# Coin_Cell_Boost.net
KiCad netlist of a schematic drawn in Altium Designer
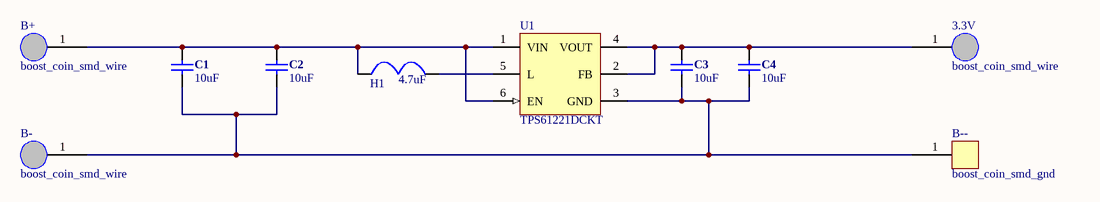
[diagram p0: Coin_Cell_Boost.SchDoc]

(export (version "E")
  (design (tool "Eeschema 10.0.6"))
  (components
    (comp (ref "3.3V")
      (value "boost_coin_smd_wire")
      (footprint "smd_pin")
      (libsource (lib "UVS-Schlib") (part "boost_coin_smd_wire"))
    )
    (comp (ref "B+")
      (value "boost_coin_smd_wire")
      (footprint "smd_pin")
      (libsource (lib "UVS-Schlib") (part "boost_coin_smd_wire"))
    )
    (comp (ref "B-")
      (value "boost_coin_smd_wire")
      (footprint "smd_pin")
      (libsource (lib "UVS-Schlib") (part "boost_coin_smd_wire"))
    )
    (comp (ref "B--")
      (value "boost_coin_smd_gnd")
      (footprint "smd_gnd")
      (libsource (lib "UVS-Schlib") (part "boost_coin_smd_gnd"))
    )
    (comp (ref "C1")
      (value "10uF")
      (footprint "CAP-0805(2012)-R")
      (description "___ OHM ___ mW 0805(2012) SMD")
      (fields
        (field (name "MANUFACTURER") "Murata Electronics North America")
        (field (name "MANUFACTURER PART NUMBER") "GRM21BR60J106ME19L")
      )
      (libsource (lib "Glove") (part "C-0805(2012)"))
    )
    (comp (ref "C2")
      (value "10uF")
      (footprint "CAP-0805(2012)-R")
      (description "___ OHM ___ mW 0805(2012) SMD")
      (fields
        (field (name "MANUFACTURER") "Murata Electronics North America")
        (field (name "MANUFACTURER PART NUMBER") "GRM21BR60J106ME19L")
      )
      (libsource (lib "Glove") (part "C-0805(2012)"))
    )
    (comp (ref "C3")
      (value "10uF")
      (footprint "CAP-0805(2012)-R")
      (description "___ OHM ___ mW 0805(2012) SMD")
      (fields
        (field (name "MANUFACTURER") "Murata Electronics North America")
        (field (name "MANUFACTURER PART NUMBER") "GRM21BR60J106ME19L")
      )
      (libsource (lib "Glove") (part "C-0805(2012)"))
    )
    (comp (ref "C4")
      (value "10uF")
      (footprint "CAP-0805(2012)-R")
      (description "___ OHM ___ mW 0805(2012) SMD")
      (fields
        (field (name "MANUFACTURER") "Murata Electronics North America")
        (field (name "MANUFACTURER PART NUMBER") "GRM21BR60J106ME19L")
      )
      (libsource (lib "Glove") (part "C-0805(2012)"))
    )
    (comp (ref "H1")
      (value "4.7uF")
      (footprint "H-0805(2012)-H")
      (fields
        (field (name "MANUFACTURER") "Murata Electronics North America")
        (field (name "MANUFACTURER PART NUMBER") "LQM21PN4R7NGRD")
        (field (name "TOLERANCE") "±30%")
      )
      (libsource (lib "Glove") (part "H-0805(2012)"))
    )
    (comp (ref "U1")
      (value "TPS61221DCKT")
      (footprint "DCK0006A_L")
      (fields (field (name "MANUFACTURER") "Texas Instruments"))
      (libsource (lib "Altium Content Vault") (part "TI-TPS61221DCK6"))
    )
  )
  (nets
    (net (code "1") (name "Net-(U1-EN)") (class "Default")
      (node (ref "B+") (pin "1") (pinfunction "1_1") (pintype "passive"))
      (node (ref "C1") (pin "1") (pinfunction "1_1") (pintype "passive"))
      (node (ref "C2") (pin "1") (pinfunction "1_1") (pintype "passive"))
      (node (ref "H1") (pin "1") (pinfunction "1_1") (pintype "passive"))
      (node (ref "U1") (pin "1") (pinfunction "VIN_1") (pintype "power_in"))
      (node (ref "U1") (pin "6") (pinfunction "EN_6") (pintype "input"))
    )
    (net (code "2") (name "Net-(U1-FB)") (class "Default")
      (node (ref "3.3V") (pin "1") (pinfunction "1_1") (pintype "passive"))
      (node (ref "C3") (pin "1") (pinfunction "1_1") (pintype "passive"))
      (node (ref "C4") (pin "1") (pinfunction "1_1") (pintype "passive"))
      (node (ref "U1") (pin "2") (pinfunction "FB_2") (pintype "passive"))
      (node (ref "U1") (pin "4") (pinfunction "VOUT_4") (pintype "power_in"))
    )
    (net (code "3") (name "Net-(U1-GND)") (class "Default")
      (node (ref "B-") (pin "1") (pinfunction "1_1") (pintype "passive"))
      (node (ref "B--") (pin "1") (pinfunction "1_1") (pintype "passive"))
      (node (ref "C1") (pin "2") (pinfunction "2_2") (pintype "passive"))
      (node (ref "C2") (pin "2") (pinfunction "2_2") (pintype "passive"))
      (node (ref "C3") (pin "2") (pinfunction "2_2") (pintype "passive"))
      (node (ref "C4") (pin "2") (pinfunction "2_2") (pintype "passive"))
      (node (ref "U1") (pin "3") (pinfunction "GND_3") (pintype "power_in"))
    )
    (net (code "4") (name "Net-(U1-L)") (class "Default")
      (node (ref "H1") (pin "2") (pinfunction "2_2") (pintype "passive"))
      (node (ref "U1") (pin "5") (pinfunction "L_5") (pintype "power_in"))
    )
  )
)
